# Differential_driver.net
KiCad netlist of a schematic drawn in EAGLE
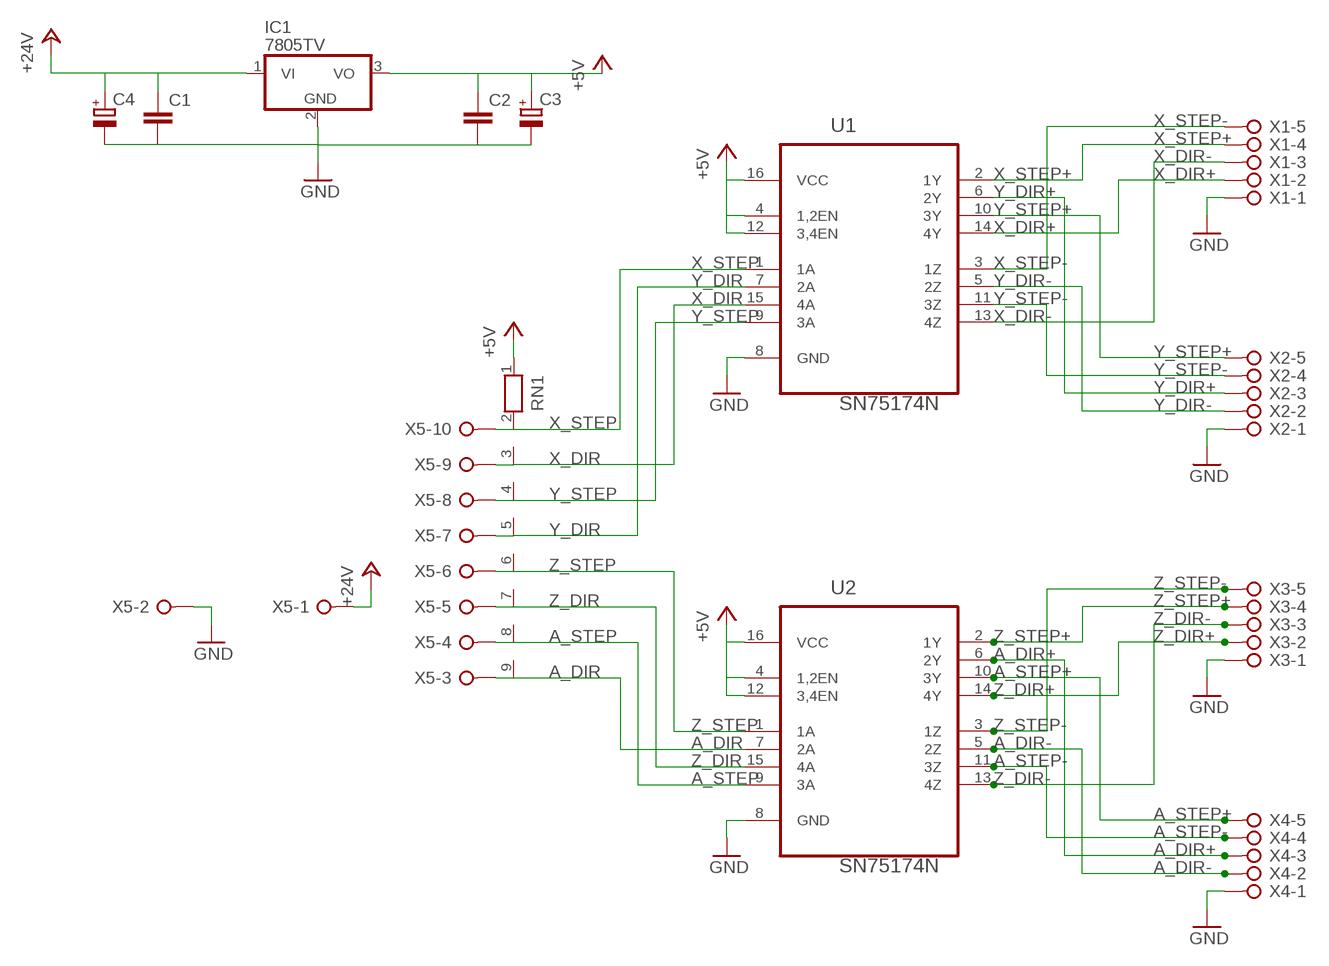
[diagram p0: schematic, sheet 1]

(export (version "E")
  (design (tool "Eeschema 10.0.6"))
  (components
    (comp (ref "C1")
      (value "C-EU025-025X050")
      (footprint "eagle-import:C025-025X050")
      (libsource (lib "eagle-import") (part "C-EU025-025X050"))
    )
    (comp (ref "C2")
      (value "C-EU025-025X050")
      (footprint "eagle-import:C025-025X050")
      (libsource (lib "eagle-import") (part "C-EU025-025X050"))
    )
    (comp (ref "C3")
      (value "CPOL-EUE2.5-5")
      (footprint "eagle-import:E2,5-5")
      (libsource (lib "eagle-import") (part "CPOL-EUE2.5-5"))
    )
    (comp (ref "C4")
      (value "CPOL-EUE2.5-5")
      (footprint "eagle-import:E2,5-5")
      (libsource (lib "eagle-import") (part "CPOL-EUE2.5-5"))
    )
    (comp (ref "IC1")
      (value "7805TV")
      (footprint "eagle-import:TO220V")
      (libsource (lib "eagle-import") (part "78TV05"))
    )
    (comp (ref "RN1")
      (value "RN08")
      (footprint "eagle-import:RN-9")
      (libsource (lib "eagle-import") (part "RN08"))
    )
    (comp (ref "U1")
      (value "SN75174N")
      (footprint "eagle-import:DIP254P762X508-16")
      (libsource (lib "eagle-import") (part "SN75174N"))
    )
    (comp (ref "U2")
      (value "SN75174N")
      (footprint "eagle-import:DIP254P762X508-16")
      (libsource (lib "eagle-import") (part "SN75174N"))
    )
    (comp (ref "X1")
      (value "W237-05P")
      (footprint "eagle-import:W237-5P")
      (libsource (lib "eagle-import") (part "W237-05P"))
    )
    (comp (ref "X2")
      (value "W237-05P")
      (footprint "eagle-import:W237-5P")
      (libsource (lib "eagle-import") (part "W237-05P"))
    )
    (comp (ref "X3")
      (value "W237-05P")
      (footprint "eagle-import:W237-5P")
      (libsource (lib "eagle-import") (part "W237-05P"))
    )
    (comp (ref "X4")
      (value "W237-05P")
      (footprint "eagle-import:W237-5P")
      (libsource (lib "eagle-import") (part "W237-05P"))
    )
    (comp (ref "X5")
      (value "W237-10P")
      (footprint "eagle-import:W237-10P")
      (libsource (lib "eagle-import") (part "W237-10P"))
    )
  )
  (nets
    (net (code "1") (name "+5V") (class "Default")
      (node (ref "C2") (pin "1") (pinfunction "1_1") (pintype "passive"))
      (node (ref "C3") (pin "+") (pinfunction "+_+") (pintype "passive"))
      (node (ref "IC1") (pin "3") (pinfunction "VO_3") (pintype "passive"))
      (node (ref "RN1") (pin "1") (pinfunction "1_1") (pintype "passive"))
      (node (ref "U1") (pin "12") (pinfunction "3,4EN_12") (pintype "input"))
      (node (ref "U1") (pin "16") (pinfunction "VCC_16") (pintype "power_in"))
      (node (ref "U1") (pin "4") (pinfunction "1,2EN_4") (pintype "input"))
      (node (ref "U2") (pin "12") (pinfunction "3,4EN_12") (pintype "input"))
      (node (ref "U2") (pin "16") (pinfunction "VCC_16") (pintype "power_in"))
      (node (ref "U2") (pin "4") (pinfunction "1,2EN_4") (pintype "input"))
    )
    (net (code "2") (name "+24V") (class "Default")
      (node (ref "C1") (pin "1") (pinfunction "1_1") (pintype "passive"))
      (node (ref "C4") (pin "+") (pinfunction "+_+") (pintype "passive"))
      (node (ref "IC1") (pin "1") (pinfunction "VI_1") (pintype "input"))
      (node (ref "X5") (pin "1") (pinfunction "KL_1") (pintype "passive"))
    )
    (net (code "3") (name "/A_DIR") (class "Default")
      (node (ref "RN1") (pin "9") (pinfunction "9_9") (pintype "passive"))
      (node (ref "U2") (pin "7") (pinfunction "2A_7") (pintype "input"))
      (node (ref "X5") (pin "3") (pinfunction "KL_3") (pintype "passive"))
    )
    (net (code "4") (name "/A_DIR+") (class "Default")
      (node (ref "U2") (pin "6") (pinfunction "2Y_6") (pintype "output"))
      (node (ref "X4") (pin "3") (pinfunction "KL_3") (pintype "passive"))
    )
    (net (code "5") (name "/A_DIR-") (class "Default")
      (node (ref "U2") (pin "5") (pinfunction "2Z_5") (pintype "output"))
      (node (ref "X4") (pin "2") (pinfunction "KL_2") (pintype "passive"))
    )
    (net (code "6") (name "/A_STEP") (class "Default")
      (node (ref "RN1") (pin "8") (pinfunction "8_8") (pintype "passive"))
      (node (ref "U2") (pin "9") (pinfunction "3A_9") (pintype "input"))
      (node (ref "X5") (pin "4") (pinfunction "KL_4") (pintype "passive"))
    )
    (net (code "7") (name "/A_STEP+") (class "Default")
      (node (ref "U2") (pin "10") (pinfunction "3Y_10") (pintype "output"))
      (node (ref "X4") (pin "5") (pinfunction "KL_5") (pintype "passive"))
    )
    (net (code "8") (name "/A_STEP-") (class "Default")
      (node (ref "U2") (pin "11") (pinfunction "3Z_11") (pintype "output"))
      (node (ref "X4") (pin "4") (pinfunction "KL_4") (pintype "passive"))
    )
    (net (code "9") (name "/X_DIR") (class "Default")
      (node (ref "RN1") (pin "3") (pinfunction "3_3") (pintype "passive"))
      (node (ref "U1") (pin "15") (pinfunction "4A_15") (pintype "input"))
      (node (ref "X5") (pin "9") (pinfunction "KL_9") (pintype "passive"))
    )
    (net (code "10") (name "/X_DIR+") (class "Default")
      (node (ref "U1") (pin "14") (pinfunction "4Y_14") (pintype "output"))
      (node (ref "X1") (pin "2") (pinfunction "KL_2") (pintype "passive"))
    )
    (net (code "11") (name "/X_DIR-") (class "Default")
      (node (ref "U1") (pin "13") (pinfunction "4Z_13") (pintype "output"))
      (node (ref "X1") (pin "3") (pinfunction "KL_3") (pintype "passive"))
    )
    (net (code "12") (name "/X_STEP") (class "Default")
      (node (ref "RN1") (pin "2") (pinfunction "2_2") (pintype "passive"))
      (node (ref "U1") (pin "1") (pinfunction "1A_1") (pintype "input"))
      (node (ref "X5") (pin "10") (pinfunction "KL_10") (pintype "passive"))
    )
    (net (code "13") (name "/X_STEP+") (class "Default")
      (node (ref "U1") (pin "2") (pinfunction "1Y_2") (pintype "output"))
      (node (ref "X1") (pin "4") (pinfunction "KL_4") (pintype "passive"))
    )
    (net (code "14") (name "/X_STEP-") (class "Default")
      (node (ref "U1") (pin "3") (pinfunction "1Z_3") (pintype "output"))
      (node (ref "X1") (pin "5") (pinfunction "KL_5") (pintype "passive"))
    )
    (net (code "15") (name "/Y_DIR") (class "Default")
      (node (ref "RN1") (pin "5") (pinfunction "5_5") (pintype "passive"))
      (node (ref "U1") (pin "7") (pinfunction "2A_7") (pintype "input"))
      (node (ref "X5") (pin "7") (pinfunction "KL_7") (pintype "passive"))
    )
    (net (code "16") (name "/Y_DIR+") (class "Default")
      (node (ref "U1") (pin "6") (pinfunction "2Y_6") (pintype "output"))
      (node (ref "X2") (pin "3") (pinfunction "KL_3") (pintype "passive"))
    )
    (net (code "17") (name "/Y_DIR-") (class "Default")
      (node (ref "U1") (pin "5") (pinfunction "2Z_5") (pintype "output"))
      (node (ref "X2") (pin "2") (pinfunction "KL_2") (pintype "passive"))
    )
    (net (code "18") (name "/Y_STEP") (class "Default")
      (node (ref "RN1") (pin "4") (pinfunction "4_4") (pintype "passive"))
      (node (ref "U1") (pin "9") (pinfunction "3A_9") (pintype "input"))
      (node (ref "X5") (pin "8") (pinfunction "KL_8") (pintype "passive"))
    )
    (net (code "19") (name "/Y_STEP+") (class "Default")
      (node (ref "U1") (pin "10") (pinfunction "3Y_10") (pintype "output"))
      (node (ref "X2") (pin "5") (pinfunction "KL_5") (pintype "passive"))
    )
    (net (code "20") (name "/Y_STEP-") (class "Default")
      (node (ref "U1") (pin "11") (pinfunction "3Z_11") (pintype "output"))
      (node (ref "X2") (pin "4") (pinfunction "KL_4") (pintype "passive"))
    )
    (net (code "21") (name "/Z_DIR") (class "Default")
      (node (ref "RN1") (pin "7") (pinfunction "7_7") (pintype "passive"))
      (node (ref "U2") (pin "15") (pinfunction "4A_15") (pintype "input"))
      (node (ref "X5") (pin "5") (pinfunction "KL_5") (pintype "passive"))
    )
    (net (code "22") (name "/Z_DIR+") (class "Default")
      (node (ref "U2") (pin "14") (pinfunction "4Y_14") (pintype "output"))
      (node (ref "X3") (pin "2") (pinfunction "KL_2") (pintype "passive"))
    )
    (net (code "23") (name "/Z_DIR-") (class "Default")
      (node (ref "U2") (pin "13") (pinfunction "4Z_13") (pintype "output"))
      (node (ref "X3") (pin "3") (pinfunction "KL_3") (pintype "passive"))
    )
    (net (code "24") (name "/Z_STEP") (class "Default")
      (node (ref "RN1") (pin "6") (pinfunction "6_6") (pintype "passive"))
      (node (ref "U2") (pin "1") (pinfunction "1A_1") (pintype "input"))
      (node (ref "X5") (pin "6") (pinfunction "KL_6") (pintype "passive"))
    )
    (net (code "25") (name "/Z_STEP+") (class "Default")
      (node (ref "U2") (pin "2") (pinfunction "1Y_2") (pintype "output"))
      (node (ref "X3") (pin "4") (pinfunction "KL_4") (pintype "passive"))
    )
    (net (code "26") (name "/Z_STEP-") (class "Default")
      (node (ref "U2") (pin "3") (pinfunction "1Z_3") (pintype "output"))
      (node (ref "X3") (pin "5") (pinfunction "KL_5") (pintype "passive"))
    )
    (net (code "27") (name "GND") (class "Default")
      (node (ref "C1") (pin "2") (pinfunction "2_2") (pintype "passive"))
      (node (ref "C2") (pin "2") (pinfunction "2_2") (pintype "passive"))
      (node (ref "C3") (pin "-") (pinfunction "-_-") (pintype "passive"))
      (node (ref "C4") (pin "-") (pinfunction "-_-") (pintype "passive"))
      (node (ref "IC1") (pin "2") (pinfunction "GND_2") (pintype "passive"))
      (node (ref "U1") (pin "8") (pinfunction "GND_8") (pintype "passive"))
      (node (ref "U2") (pin "8") (pinfunction "GND_8") (pintype "passive"))
      (node (ref "X1") (pin "1") (pinfunction "KL_1") (pintype "passive"))
      (node (ref "X2") (pin "1") (pinfunction "KL_1") (pintype "passive"))
      (node (ref "X3") (pin "1") (pinfunction "KL_1") (pintype "passive"))
      (node (ref "X4") (pin "1") (pinfunction "KL_1") (pintype "passive"))
      (node (ref "X5") (pin "2") (pinfunction "KL_2") (pintype "passive"))
    )
  )
)
